# BMS_Rev_1.net
KiCad netlist of a schematic drawn in EAGLE
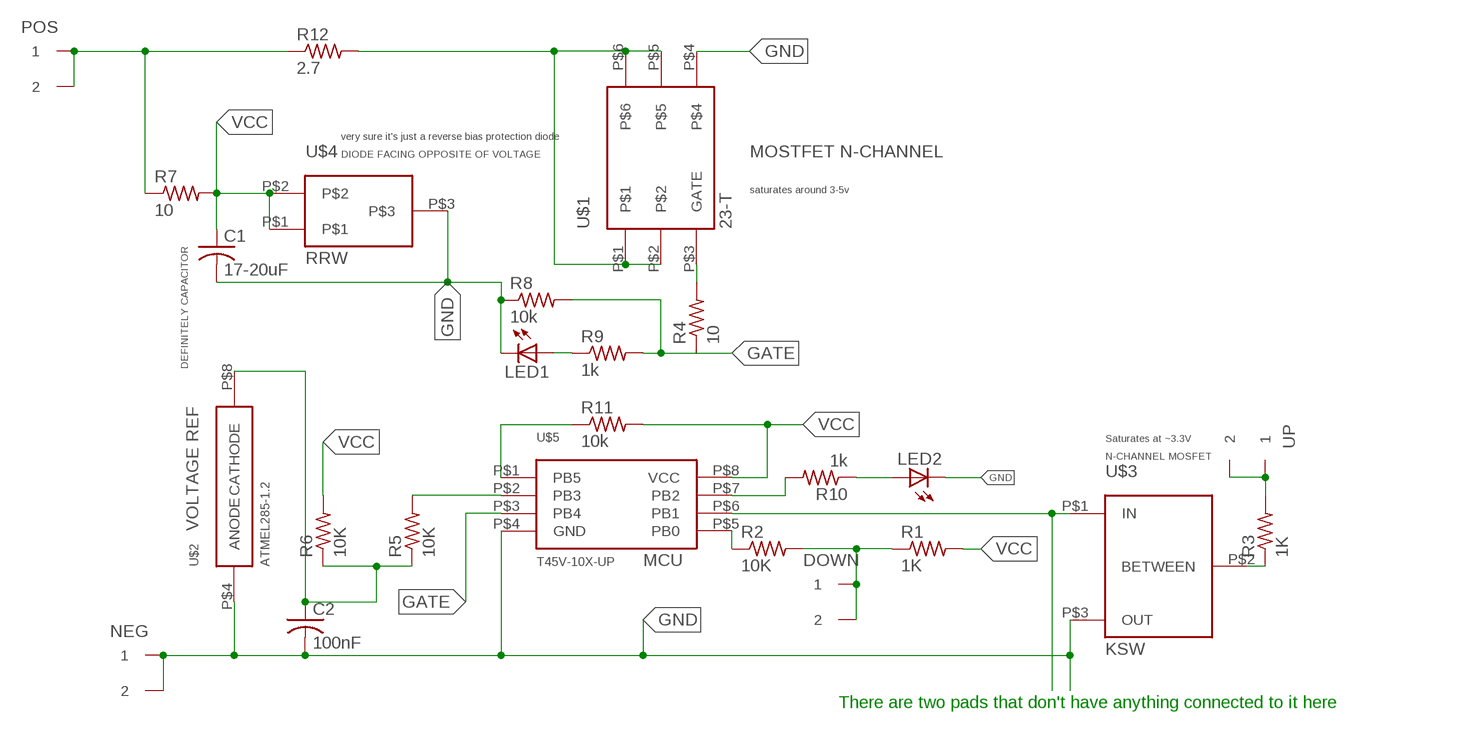
[diagram p0: schematic, sheet 1]

(export (version "E")
  (design (tool "Eeschema 10.0.6"))
  (components
    (comp (ref "C1")
      (value "17-20uF")
      (footprint "eagle-import:C0805")
      (libsource (lib "eagle-import") (part "C-USC0805"))
    )
    (comp (ref "C2")
      (value "100nF")
      (footprint "eagle-import:C0805")
      (libsource (lib "eagle-import") (part "C-USC0805"))
    )
    (comp (ref "DOWN")
      (value "CONN_1")
      (footprint "eagle-import:CONNECTOR_1")
      (libsource (lib "eagle-import") (part "CONN_1"))
    )
    (comp (ref "LED1")
      (value "LEDCHIPLED_1206")
      (footprint "eagle-import:CHIPLED_1206")
      (libsource (lib "eagle-import") (part "LEDCHIPLED_1206"))
    )
    (comp (ref "LED2")
      (value "LEDCHIPLED_1206")
      (footprint "eagle-import:CHIPLED_1206")
      (libsource (lib "eagle-import") (part "LEDCHIPLED_1206"))
    )
    (comp (ref "NEG")
      (value "CONN_1")
      (footprint "eagle-import:CONNECTOR_1")
      (libsource (lib "eagle-import") (part "CONN_1"))
    )
    (comp (ref "POS")
      (value "CONN_1")
      (footprint "eagle-import:CONNECTOR_1")
      (libsource (lib "eagle-import") (part "CONN_1"))
    )
    (comp (ref "R1")
      (value "1K")
      (footprint "eagle-import:R0805")
      (libsource (lib "eagle-import") (part "R-US_R0805"))
    )
    (comp (ref "R2")
      (value "10K")
      (footprint "eagle-import:R0805")
      (libsource (lib "eagle-import") (part "R-US_R0805"))
    )
    (comp (ref "R3")
      (value "1K")
      (footprint "eagle-import:R0805")
      (libsource (lib "eagle-import") (part "R-US_R0805"))
    )
    (comp (ref "R4")
      (value "10")
      (footprint "eagle-import:R0805")
      (libsource (lib "eagle-import") (part "R-US_R0805"))
    )
    (comp (ref "R5")
      (value "10K")
      (footprint "eagle-import:R0805")
      (libsource (lib "eagle-import") (part "R-US_R0805"))
    )
    (comp (ref "R6")
      (value "10K")
      (footprint "eagle-import:R0805")
      (libsource (lib "eagle-import") (part "R-US_R0805"))
    )
    (comp (ref "R7")
      (value "10")
      (footprint "eagle-import:R0805")
      (libsource (lib "eagle-import") (part "R-US_R0805"))
    )
    (comp (ref "R8")
      (value "10k")
      (footprint "eagle-import:R0805")
      (libsource (lib "eagle-import") (part "R-US_R0805"))
    )
    (comp (ref "R9")
      (value "1k")
      (footprint "eagle-import:R0805")
      (libsource (lib "eagle-import") (part "R-US_R0805"))
    )
    (comp (ref "R10")
      (value "1k")
      (footprint "eagle-import:R0805")
      (libsource (lib "eagle-import") (part "R-US_R0805"))
    )
    (comp (ref "R11")
      (value "10k")
      (footprint "eagle-import:R0805")
      (libsource (lib "eagle-import") (part "R-US_R0805"))
    )
    (comp (ref "R12")
      (value "2.7")
      (footprint "eagle-import:R0805")
      (libsource (lib "eagle-import") (part "R-US_R0805"))
    )
    (comp (ref "U$1")
      (value "23-T")
      (footprint "eagle-import:SOT-23-6")
      (libsource (lib "eagle-import") (part "23-T"))
    )
    (comp (ref "U$2")
      (value "ATMEL285-1.2")
      (footprint "eagle-import:8-SOIC")
      (libsource (lib "eagle-import") (part "ATMEL285-1.2"))
    )
    (comp (ref "U$3")
      (value "KSW")
      (footprint "eagle-import:SOT23-3")
      (libsource (lib "eagle-import") (part "KSW"))
    )
    (comp (ref "U$4")
      (value "RRW")
      (footprint "eagle-import:SOT23-3")
      (libsource (lib "eagle-import") (part "RRW"))
    )
    (comp (ref "U$5")
      (value "T45V-10X-UP")
      (footprint "eagle-import:TSOP-8")
      (libsource (lib "eagle-import") (part "T45V-10X-UP"))
    )
    (comp (ref "UP")
      (value "CONN_1")
      (footprint "eagle-import:CONNECTOR_1")
      (libsource (lib "eagle-import") (part "CONN_1"))
    )
  )
  (nets
    (net (code "1") (name "GATE") (class "Default")
      (node (ref "R4") (pin "1") (pinfunction "1_1") (pintype "passive"))
      (node (ref "R8") (pin "2") (pinfunction "2_2") (pintype "passive"))
      (node (ref "R9") (pin "2") (pinfunction "2_2") (pintype "passive"))
      (node (ref "U$5") (pin "P$3") (pinfunction "PB4_P$3") (pintype "bidirectional"))
    )
    (net (code "2") (name "GND") (class "Default")
      (node (ref "C1") (pin "2") (pinfunction "2_2") (pintype "passive"))
      (node (ref "C2") (pin "2") (pinfunction "2_2") (pintype "passive"))
      (node (ref "LED1") (pin "C") (pinfunction "C_C") (pintype "passive"))
      (node (ref "LED2") (pin "C") (pinfunction "C_C") (pintype "passive"))
      (node (ref "NEG") (pin "1") (pinfunction "1_1") (pintype "bidirectional"))
      (node (ref "NEG") (pin "2") (pinfunction "2_2") (pintype "bidirectional"))
      (node (ref "R8") (pin "1") (pinfunction "1_1") (pintype "passive"))
      (node (ref "U$1") (pin "P$4") (pinfunction "P$4_P$4") (pintype "bidirectional"))
      (node (ref "U$2") (pin "P$4") (pinfunction "ANODE_P$4") (pintype "bidirectional"))
      (node (ref "U$3") (pin "P$3") (pinfunction "OUT_P$3") (pintype "bidirectional"))
      (node (ref "U$4") (pin "P$3") (pinfunction "P$3_P$3") (pintype "bidirectional"))
      (node (ref "U$5") (pin "P$4") (pinfunction "GND_P$4") (pintype "bidirectional"))
    )
    (net (code "3") (name "Net-(DOWN-Pad1)") (class "Default")
      (node (ref "DOWN") (pin "1") (pinfunction "1_1") (pintype "bidirectional"))
      (node (ref "DOWN") (pin "2") (pinfunction "2_2") (pintype "bidirectional"))
      (node (ref "R1") (pin "1") (pinfunction "1_1") (pintype "passive"))
      (node (ref "R2") (pin "2") (pinfunction "2_2") (pintype "passive"))
    )
    (net (code "4") (name "Net-(LED1-PadA)") (class "Default")
      (node (ref "LED1") (pin "A") (pinfunction "A_A") (pintype "passive"))
      (node (ref "R9") (pin "1") (pinfunction "1_1") (pintype "passive"))
    )
    (net (code "5") (name "Net-(LED2-PadA)") (class "Default")
      (node (ref "LED2") (pin "A") (pinfunction "A_A") (pintype "passive"))
      (node (ref "R10") (pin "1") (pinfunction "1_1") (pintype "passive"))
    )
    (net (code "6") (name "Net-(POS-Pad1)") (class "Default")
      (node (ref "POS") (pin "1") (pinfunction "1_1") (pintype "bidirectional"))
      (node (ref "POS") (pin "2") (pinfunction "2_2") (pintype "bidirectional"))
      (node (ref "R12") (pin "1") (pinfunction "1_1") (pintype "passive"))
      (node (ref "R7") (pin "1") (pinfunction "1_1") (pintype "passive"))
    )
    (net (code "7") (name "Net-(R3-Pad2)") (class "Default")
      (node (ref "R3") (pin "2") (pinfunction "2_2") (pintype "passive"))
      (node (ref "UP") (pin "1") (pinfunction "1_1") (pintype "bidirectional"))
      (node (ref "UP") (pin "2") (pinfunction "2_2") (pintype "bidirectional"))
    )
    (net (code "8") (name "Net-(R12-Pad2)") (class "Default")
      (node (ref "R12") (pin "2") (pinfunction "2_2") (pintype "passive"))
      (node (ref "U$1") (pin "P$1") (pinfunction "P$1_P$1") (pintype "bidirectional"))
      (node (ref "U$1") (pin "P$2") (pinfunction "P$2_P$2") (pintype "bidirectional"))
      (node (ref "U$1") (pin "P$5") (pinfunction "P$5_P$5") (pintype "bidirectional"))
      (node (ref "U$1") (pin "P$6") (pinfunction "P$6_P$6") (pintype "bidirectional"))
    )
    (net (code "9") (name "Net-(U$1-GATE)") (class "Default")
      (node (ref "R4") (pin "2") (pinfunction "2_2") (pintype "passive"))
      (node (ref "U$1") (pin "P$3") (pinfunction "GATE_P$3") (pintype "bidirectional"))
    )
    (net (code "10") (name "Net-(U$2-CATHODE)") (class "Default")
      (node (ref "C2") (pin "1") (pinfunction "1_1") (pintype "passive"))
      (node (ref "R5") (pin "1") (pinfunction "1_1") (pintype "passive"))
      (node (ref "R6") (pin "1") (pinfunction "1_1") (pintype "passive"))
      (node (ref "U$2") (pin "P$8") (pinfunction "CATHODE_P$8") (pintype "bidirectional"))
    )
    (net (code "11") (name "Net-(U$3-BETWEEN)") (class "Default")
      (node (ref "R3") (pin "1") (pinfunction "1_1") (pintype "passive"))
      (node (ref "U$3") (pin "P$2") (pinfunction "BETWEEN_P$2") (pintype "bidirectional"))
    )
    (net (code "12") (name "Net-(U$3-IN)") (class "Default")
      (node (ref "U$3") (pin "P$1") (pinfunction "IN_P$1") (pintype "bidirectional"))
      (node (ref "U$5") (pin "P$6") (pinfunction "PB1_P$6") (pintype "bidirectional"))
    )
    (net (code "13") (name "Net-(U$5-PB0)") (class "Default")
      (node (ref "R2") (pin "1") (pinfunction "1_1") (pintype "passive"))
      (node (ref "U$5") (pin "P$5") (pinfunction "PB0_P$5") (pintype "bidirectional"))
    )
    (net (code "14") (name "Net-(U$5-PB2)") (class "Default")
      (node (ref "R10") (pin "2") (pinfunction "2_2") (pintype "passive"))
      (node (ref "U$5") (pin "P$7") (pinfunction "PB2_P$7") (pintype "bidirectional"))
    )
    (net (code "15") (name "Net-(U$5-PB3)") (class "Default")
      (node (ref "R5") (pin "2") (pinfunction "2_2") (pintype "passive"))
      (node (ref "U$5") (pin "P$2") (pinfunction "PB3_P$2") (pintype "bidirectional"))
    )
    (net (code "16") (name "Net-(U$5-PB5)") (class "Default")
      (node (ref "R11") (pin "1") (pinfunction "1_1") (pintype "passive"))
      (node (ref "U$5") (pin "P$1") (pinfunction "PB5_P$1") (pintype "bidirectional"))
    )
    (net (code "17") (name "VCC") (class "Default")
      (node (ref "C1") (pin "1") (pinfunction "1_1") (pintype "passive"))
      (node (ref "R1") (pin "2") (pinfunction "2_2") (pintype "passive"))
      (node (ref "R11") (pin "2") (pinfunction "2_2") (pintype "passive"))
      (node (ref "R6") (pin "2") (pinfunction "2_2") (pintype "passive"))
      (node (ref "R7") (pin "2") (pinfunction "2_2") (pintype "passive"))
      (node (ref "U$4") (pin "P$1") (pinfunction "P$1_P$1") (pintype "bidirectional"))
      (node (ref "U$4") (pin "P$2") (pinfunction "P$2_P$2") (pintype "bidirectional"))
      (node (ref "U$5") (pin "P$8") (pinfunction "VCC_P$8") (pintype "bidirectional"))
    )
  )
)
